# 27C128_adapter.net
KiCad netlist of a schematic drawn in EAGLE
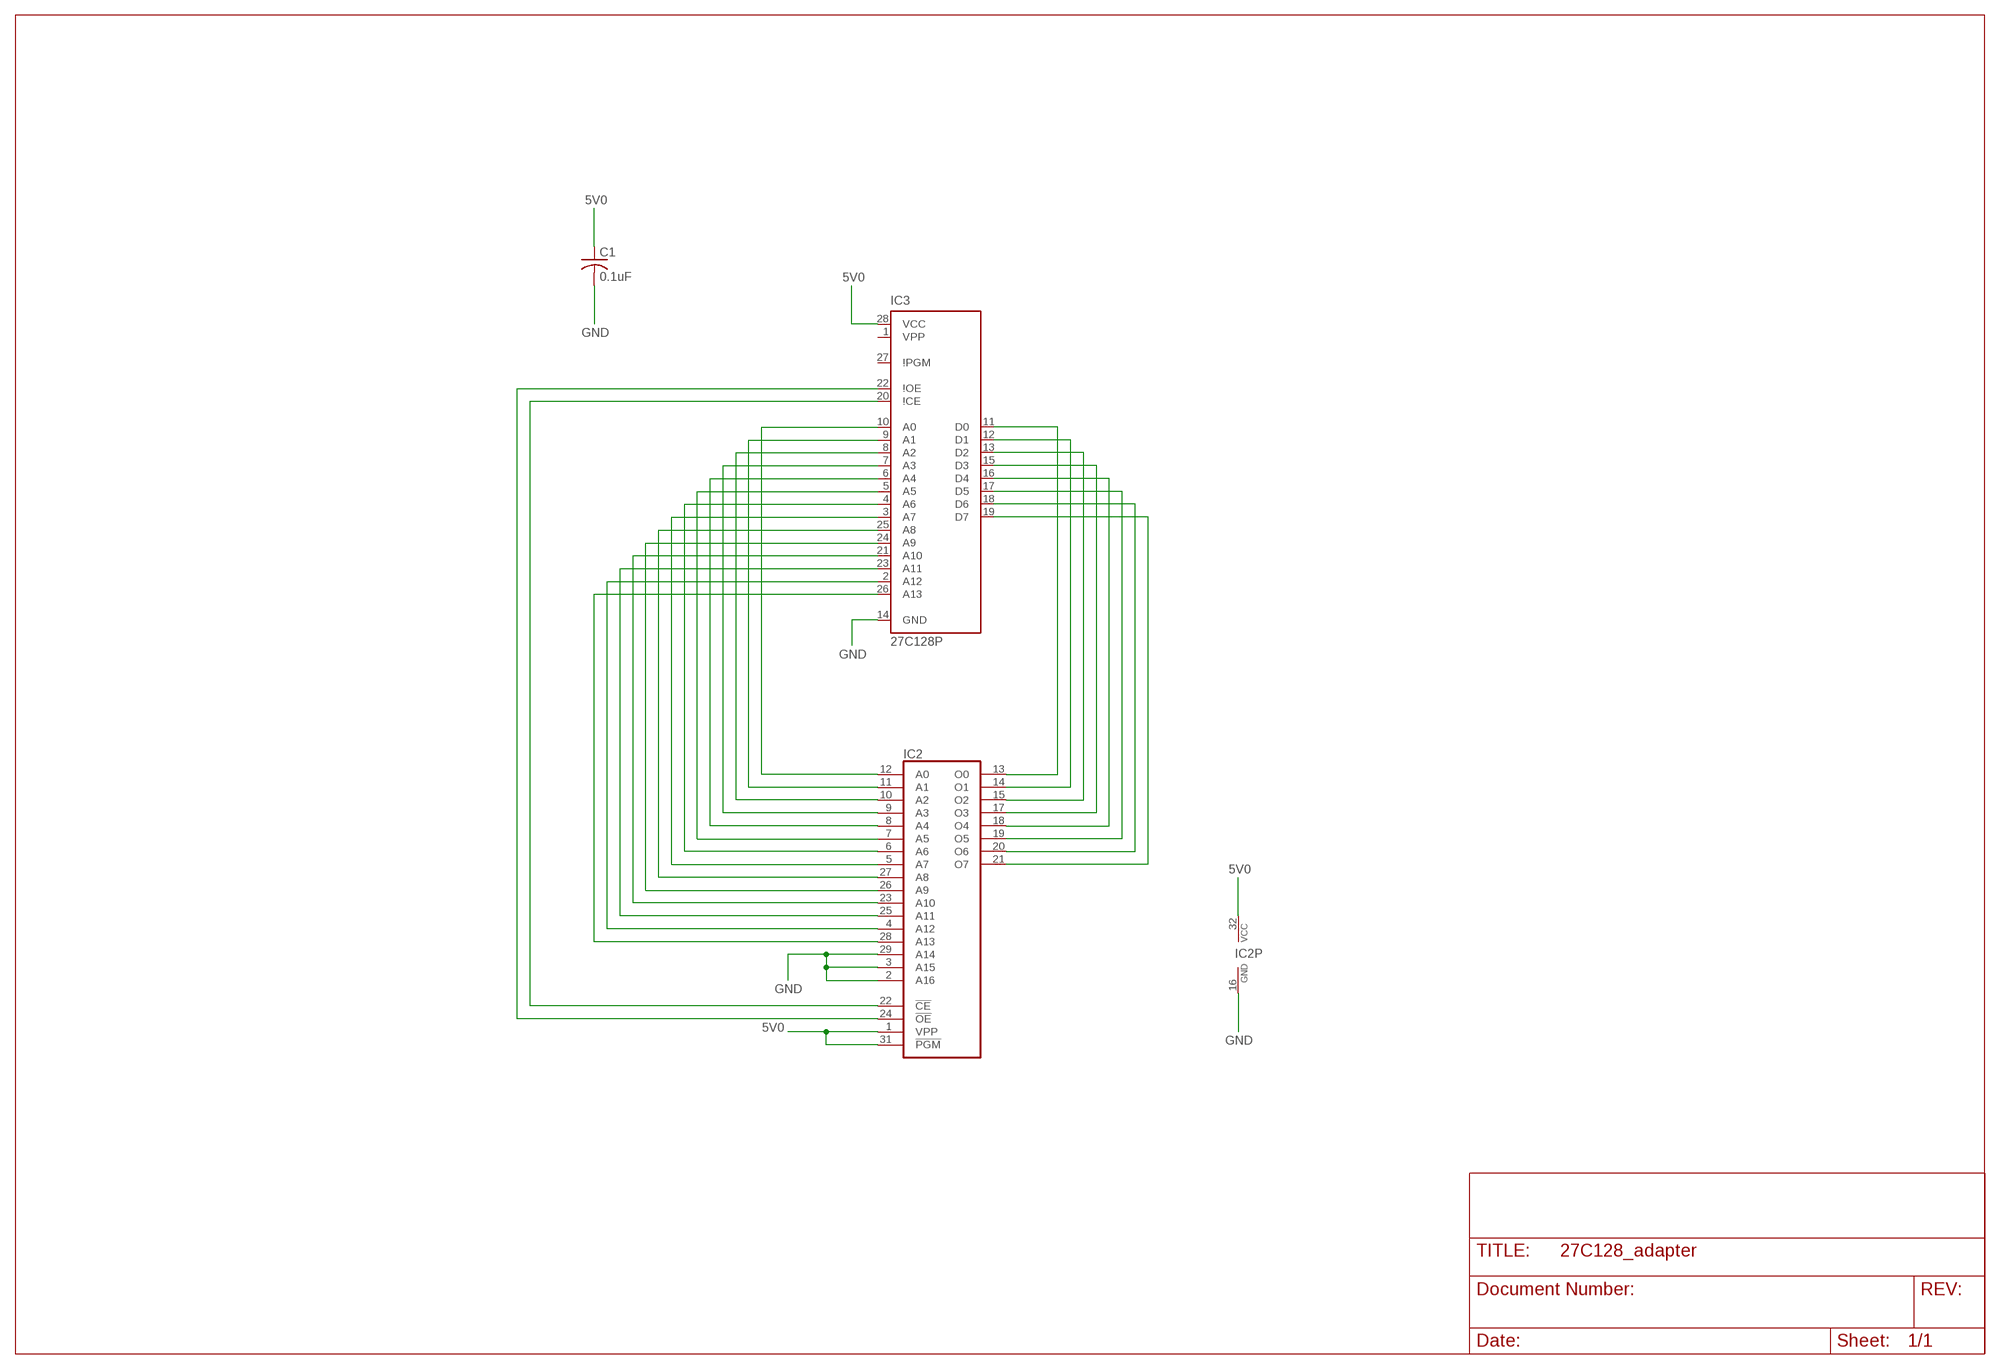
[diagram p0: schematic, sheet 1]

(export (version "E")
  (design (tool "Eeschema 10.0.6"))
  (components
    (comp (ref "C1")
      (value "0.1uF")
      (footprint "eagle-import:C0603K")
      (libsource (lib "eagle-import") (part "C-USC0603K"))
    )
    (comp (ref "IC2")
      (value "27010PLCC32")
      (footprint "eagle-import:PLCC32R")
      (libsource (lib "eagle-import") (part "27010PLCC32"))
    )
    (comp (ref "IC3")
      (value "27C128P")
      (footprint "eagle-import:DIL28-6")
      (libsource (lib "eagle-import") (part "27128PC"))
    )
  )
  (nets
    (net (code "1") (name "/5V0") (class "Default")
      (node (ref "C1") (pin "1") (pinfunction "1_1") (pintype "passive"))
      (node (ref "IC2") (pin "1") (pinfunction "VPP_1") (pintype "input"))
      (node (ref "IC2") (pin "31") (pinfunction "~{PGM}_31") (pintype "input"))
      (node (ref "IC2") (pin "32") (pinfunction "VCC_32") (pintype "power_in"))
      (node (ref "IC3") (pin "28") (pinfunction "VCC_28") (pintype "power_in"))
    )
    (net (code "2") (name "/GND") (class "Default")
      (node (ref "C1") (pin "2") (pinfunction "2_2") (pintype "passive"))
      (node (ref "IC2") (pin "16") (pinfunction "GND_16") (pintype "power_in"))
      (node (ref "IC2") (pin "2") (pinfunction "A16_2") (pintype "input"))
      (node (ref "IC2") (pin "29") (pinfunction "A14_29") (pintype "input"))
      (node (ref "IC2") (pin "3") (pinfunction "A15_3") (pintype "input"))
      (node (ref "IC3") (pin "14") (pinfunction "GND_14") (pintype "power_in"))
    )
    (net (code "3") (name "Net-(IC2A-A0)") (class "Default")
      (node (ref "IC2") (pin "12") (pinfunction "A0_12") (pintype "input"))
      (node (ref "IC3") (pin "10") (pinfunction "A0_10") (pintype "input"))
    )
    (net (code "4") (name "Net-(IC2A-A1)") (class "Default")
      (node (ref "IC2") (pin "11") (pinfunction "A1_11") (pintype "input"))
      (node (ref "IC3") (pin "9") (pinfunction "A1_9") (pintype "input"))
    )
    (net (code "5") (name "Net-(IC2A-A2)") (class "Default")
      (node (ref "IC2") (pin "10") (pinfunction "A2_10") (pintype "input"))
      (node (ref "IC3") (pin "8") (pinfunction "A2_8") (pintype "input"))
    )
    (net (code "6") (name "Net-(IC2A-A3)") (class "Default")
      (node (ref "IC2") (pin "9") (pinfunction "A3_9") (pintype "input"))
      (node (ref "IC3") (pin "7") (pinfunction "A3_7") (pintype "input"))
    )
    (net (code "7") (name "Net-(IC2A-A4)") (class "Default")
      (node (ref "IC2") (pin "8") (pinfunction "A4_8") (pintype "input"))
      (node (ref "IC3") (pin "6") (pinfunction "A4_6") (pintype "input"))
    )
    (net (code "8") (name "Net-(IC2A-A5)") (class "Default")
      (node (ref "IC2") (pin "7") (pinfunction "A5_7") (pintype "input"))
      (node (ref "IC3") (pin "5") (pinfunction "A5_5") (pintype "input"))
    )
    (net (code "9") (name "Net-(IC2A-A6)") (class "Default")
      (node (ref "IC2") (pin "6") (pinfunction "A6_6") (pintype "input"))
      (node (ref "IC3") (pin "4") (pinfunction "A6_4") (pintype "input"))
    )
    (net (code "10") (name "Net-(IC2A-A7)") (class "Default")
      (node (ref "IC2") (pin "5") (pinfunction "A7_5") (pintype "input"))
      (node (ref "IC3") (pin "3") (pinfunction "A7_3") (pintype "input"))
    )
    (net (code "11") (name "Net-(IC2A-A8)") (class "Default")
      (node (ref "IC2") (pin "27") (pinfunction "A8_27") (pintype "input"))
      (node (ref "IC3") (pin "25") (pinfunction "A8_25") (pintype "input"))
    )
    (net (code "12") (name "Net-(IC2A-A9)") (class "Default")
      (node (ref "IC2") (pin "26") (pinfunction "A9_26") (pintype "input"))
      (node (ref "IC3") (pin "24") (pinfunction "A9_24") (pintype "input"))
    )
    (net (code "13") (name "Net-(IC2A-A10)") (class "Default")
      (node (ref "IC2") (pin "23") (pinfunction "A10_23") (pintype "input"))
      (node (ref "IC3") (pin "21") (pinfunction "A10_21") (pintype "input"))
    )
    (net (code "14") (name "Net-(IC2A-A11)") (class "Default")
      (node (ref "IC2") (pin "25") (pinfunction "A11_25") (pintype "input"))
      (node (ref "IC3") (pin "23") (pinfunction "A11_23") (pintype "input"))
    )
    (net (code "15") (name "Net-(IC2A-A12)") (class "Default")
      (node (ref "IC2") (pin "4") (pinfunction "A12_4") (pintype "input"))
      (node (ref "IC3") (pin "2") (pinfunction "A12_2") (pintype "input"))
    )
    (net (code "16") (name "Net-(IC2A-A13)") (class "Default")
      (node (ref "IC2") (pin "28") (pinfunction "A13_28") (pintype "input"))
      (node (ref "IC3") (pin "26") (pinfunction "A13_26") (pintype "input"))
    )
    (net (code "17") (name "Net-(IC2A-O0)") (class "Default")
      (node (ref "IC2") (pin "13") (pinfunction "O0_13") (pintype "tri_state"))
      (node (ref "IC3") (pin "11") (pinfunction "D0_11") (pintype "tri_state"))
    )
    (net (code "18") (name "Net-(IC2A-O1)") (class "Default")
      (node (ref "IC2") (pin "14") (pinfunction "O1_14") (pintype "tri_state"))
      (node (ref "IC3") (pin "12") (pinfunction "D1_12") (pintype "tri_state"))
    )
    (net (code "19") (name "Net-(IC2A-O2)") (class "Default")
      (node (ref "IC2") (pin "15") (pinfunction "O2_15") (pintype "tri_state"))
      (node (ref "IC3") (pin "13") (pinfunction "D2_13") (pintype "tri_state"))
    )
    (net (code "20") (name "Net-(IC2A-O3)") (class "Default")
      (node (ref "IC2") (pin "17") (pinfunction "O3_17") (pintype "tri_state"))
      (node (ref "IC3") (pin "15") (pinfunction "D3_15") (pintype "tri_state"))
    )
    (net (code "21") (name "Net-(IC2A-O4)") (class "Default")
      (node (ref "IC2") (pin "18") (pinfunction "O4_18") (pintype "tri_state"))
      (node (ref "IC3") (pin "16") (pinfunction "D4_16") (pintype "tri_state"))
    )
    (net (code "22") (name "Net-(IC2A-O5)") (class "Default")
      (node (ref "IC2") (pin "19") (pinfunction "O5_19") (pintype "tri_state"))
      (node (ref "IC3") (pin "17") (pinfunction "D5_17") (pintype "tri_state"))
    )
    (net (code "23") (name "Net-(IC2A-O6)") (class "Default")
      (node (ref "IC2") (pin "20") (pinfunction "O6_20") (pintype "tri_state"))
      (node (ref "IC3") (pin "18") (pinfunction "D6_18") (pintype "tri_state"))
    )
    (net (code "24") (name "Net-(IC2A-O7)") (class "Default")
      (node (ref "IC2") (pin "21") (pinfunction "O7_21") (pintype "tri_state"))
      (node (ref "IC3") (pin "19") (pinfunction "D7_19") (pintype "tri_state"))
    )
    (net (code "25") (name "Net-(IC2A-~{CE})") (class "Default")
      (node (ref "IC2") (pin "22") (pinfunction "~{CE}_22") (pintype "input"))
      (node (ref "IC3") (pin "20") (pinfunction "\\~{CE}_20") (pintype "input"))
    )
    (net (code "26") (name "Net-(IC2A-~{OE})") (class "Default")
      (node (ref "IC2") (pin "24") (pinfunction "~{OE}_24") (pintype "input"))
      (node (ref "IC3") (pin "22") (pinfunction "\\~{OE}_22") (pintype "input"))
    )
    (net (code "27") (name "unconnected-(IC3-VPP-Pad1)") (class "Default")
      (node (ref "IC3") (pin "1") (pinfunction "VPP_1") (pintype "input"))
    )
    (net (code "28") (name "unconnected-(IC3-\\~{PGM}-Pad27)") (class "Default")
      (node (ref "IC3") (pin "27") (pinfunction "\\~{PGM}_27") (pintype "passive"))
    )
  )
)
